# Flash-Memory.net
KiCad netlist of a schematic drawn in Altium Designer
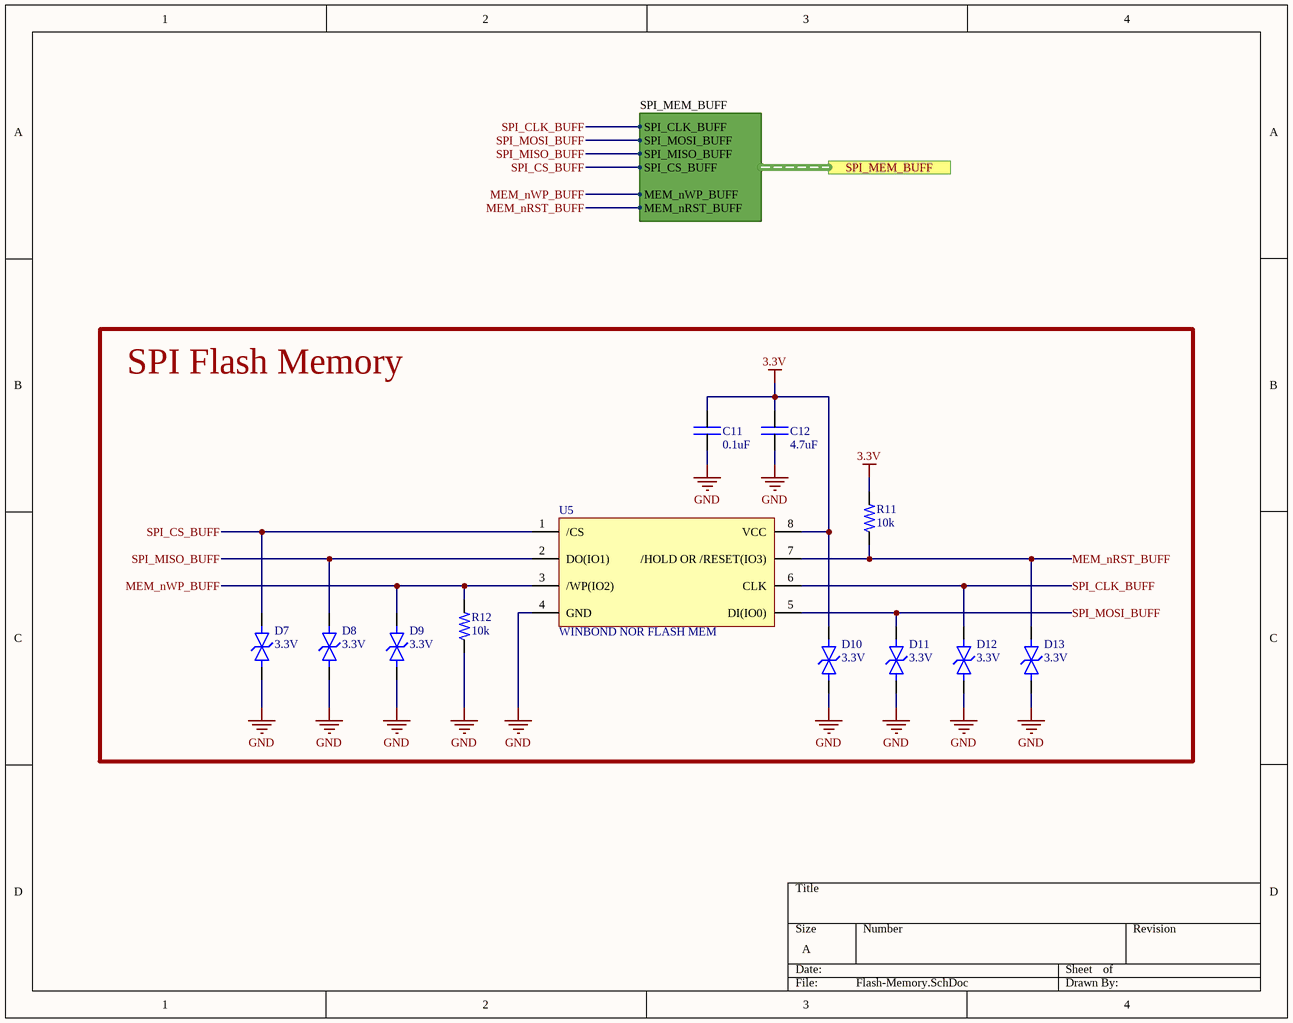
[diagram p0: Flash-Memory.SchDoc]

(export (version "E")
  (design (tool "Eeschema 10.0.6"))
  (components
    (comp (ref "C11")
      (value "0.1uF")
      (footprint "Christmas-2024_TSO-PCB:0402C")
      (description "Capacitor")
      (fields (field (name "MFR") "Samsung") (field (name "Comment") "CAP"))
      (libsource (lib "Christmas-2024_TSO-PCB") (part "CAP"))
    )
    (comp (ref "C12")
      (value "4.7uF")
      (footprint "Christmas-2024_TSO-PCB:0402C")
      (description "Capacitor")
      (fields (field (name "MFR") "Samsung") (field (name "Comment") "CAP"))
      (libsource (lib "Christmas-2024_TSO-PCB") (part "CAP"))
    )
    (comp (ref "D7")
      (value "DESD3V3E1BL-7B")
      (footprint "Christmas-2024_TSO-PCB:0402-TVS")
      (description "TVS DIODE 3.3VWM 7VC DFN1006-2")
      (fields (field (name "MFR") "Diodes Incorporated") (field (name "VRS") "3.3V"))
      (libsource (lib "Christmas-2024_TSO-PCB") (part "TVS Diode 3.3V Bi"))
    )
    (comp (ref "D8")
      (value "DESD3V3E1BL-7B")
      (footprint "Christmas-2024_TSO-PCB:0402-TVS")
      (description "TVS DIODE 3.3VWM 7VC DFN1006-2")
      (fields (field (name "MFR") "Diodes Incorporated") (field (name "VRS") "3.3V"))
      (libsource (lib "Christmas-2024_TSO-PCB") (part "TVS Diode 3.3V Bi"))
    )
    (comp (ref "D9")
      (value "DESD3V3E1BL-7B")
      (footprint "Christmas-2024_TSO-PCB:0402-TVS")
      (description "TVS DIODE 3.3VWM 7VC DFN1006-2")
      (fields (field (name "MFR") "Diodes Incorporated") (field (name "VRS") "3.3V"))
      (libsource (lib "Christmas-2024_TSO-PCB") (part "TVS Diode 3.3V Bi"))
    )
    (comp (ref "D10")
      (value "DESD3V3E1BL-7B")
      (footprint "Christmas-2024_TSO-PCB:0402-TVS")
      (description "TVS DIODE 3.3VWM 7VC DFN1006-2")
      (fields (field (name "MFR") "Diodes Incorporated") (field (name "VRS") "3.3V"))
      (libsource (lib "Christmas-2024_TSO-PCB") (part "TVS Diode 3.3V Bi"))
    )
    (comp (ref "D11")
      (value "DESD3V3E1BL-7B")
      (footprint "Christmas-2024_TSO-PCB:0402-TVS")
      (description "TVS DIODE 3.3VWM 7VC DFN1006-2")
      (fields (field (name "MFR") "Diodes Incorporated") (field (name "VRS") "3.3V"))
      (libsource (lib "Christmas-2024_TSO-PCB") (part "TVS Diode 3.3V Bi"))
    )
    (comp (ref "D12")
      (value "DESD3V3E1BL-7B")
      (footprint "Christmas-2024_TSO-PCB:0402-TVS")
      (description "TVS DIODE 3.3VWM 7VC DFN1006-2")
      (fields (field (name "MFR") "Diodes Incorporated") (field (name "VRS") "3.3V"))
      (libsource (lib "Christmas-2024_TSO-PCB") (part "TVS Diode 3.3V Bi"))
    )
    (comp (ref "D13")
      (value "DESD3V3E1BL-7B")
      (footprint "Christmas-2024_TSO-PCB:0402-TVS")
      (description "TVS DIODE 3.3VWM 7VC DFN1006-2")
      (fields (field (name "MFR") "Diodes Incorporated") (field (name "VRS") "3.3V"))
      (libsource (lib "Christmas-2024_TSO-PCB") (part "TVS Diode 3.3V Bi"))
    )
    (comp (ref "R11")
      (value "10k")
      (footprint "Christmas-2024_TSO-PCB:0402R")
      (description "Resistor")
      (fields (field (name "MFR") "YAGEO") (field (name "Comment") "RES"))
      (libsource (lib "Christmas-2024_TSO-PCB") (part "RES"))
    )
    (comp (ref "R12")
      (value "10k")
      (footprint "Christmas-2024_TSO-PCB:0402R")
      (description "Resistor")
      (fields (field (name "MFR") "YAGEO") (field (name "Comment") "RES"))
      (libsource (lib "Christmas-2024_TSO-PCB") (part "RES"))
    )
    (comp (ref "U5")
      (value "WINBOND NOR FLASH MEM")
      (footprint "Christmas-2024_TSO-PCB:8-SOIC")
      (description "FLASH - NOR Memory IC SPI, 128 Mbit")
      (fields (field (name "MFR") "Winbond"))
      (libsource (lib "Christmas-2024_TSO-PCB") (part "WINBOND NOR FLASH MEM"))
    )
  )
  (nets
    (net (code "2") (name "/MEM_nRST_BUFF") (class "Default")
      (node (ref "D13") (pin "1") (pinfunction "1_1") (pintype "passive"))
      (node (ref "R11") (pin "1") (pinfunction "1_1") (pintype "passive"))
      (node (ref "U5") (pin "7") (pinfunction "/HOLD_OR_/RESET(IO3)_7") (pintype "passive"))
    )
    (net (code "3") (name "/MEM_nWP_BUFF") (class "Default")
      (node (ref "D9") (pin "1") (pinfunction "1_1") (pintype "passive"))
      (node (ref "R12") (pin "2") (pinfunction "2_2") (pintype "passive"))
      (node (ref "U5") (pin "3") (pinfunction "/WP(IO2)_3") (pintype "passive"))
    )
    (net (code "4") (name "/SPI_CLK_BUFF") (class "Default")
      (node (ref "D12") (pin "1") (pinfunction "1_1") (pintype "passive"))
      (node (ref "U5") (pin "6") (pinfunction "CLK_6") (pintype "passive"))
    )
    (net (code "5") (name "/SPI_CS_BUFF") (class "Default")
      (node (ref "D7") (pin "1") (pinfunction "1_1") (pintype "passive"))
      (node (ref "U5") (pin "1") (pinfunction "/CS_1") (pintype "passive"))
    )
    (net (code "6") (name "/SPI_MISO_BUFF") (class "Default")
      (node (ref "D8") (pin "1") (pinfunction "1_1") (pintype "passive"))
      (node (ref "U5") (pin "2") (pinfunction "DO(IO1)_2") (pintype "passive"))
    )
    (net (code "7") (name "/SPI_MOSI_BUFF") (class "Default")
      (node (ref "D11") (pin "1") (pinfunction "1_1") (pintype "passive"))
      (node (ref "U5") (pin "5") (pinfunction "DI(IO0)_5") (pintype "passive"))
    )
    (net (code "9") (name "3.3V") (class "Default")
      (node (ref "C11") (pin "2") (pinfunction "2_2") (pintype "passive"))
      (node (ref "C12") (pin "2") (pinfunction "2_2") (pintype "passive"))
      (node (ref "D10") (pin "1") (pinfunction "1_1") (pintype "passive"))
      (node (ref "R11") (pin "2") (pinfunction "2_2") (pintype "passive"))
      (node (ref "U5") (pin "8") (pinfunction "VCC_8") (pintype "power_in"))
    )
    (net (code "10") (name "GND") (class "Default")
      (node (ref "C11") (pin "1") (pinfunction "1_1") (pintype "passive"))
      (node (ref "C12") (pin "1") (pinfunction "1_1") (pintype "passive"))
      (node (ref "D10") (pin "2") (pinfunction "2_2") (pintype "passive"))
      (node (ref "D11") (pin "2") (pinfunction "2_2") (pintype "passive"))
      (node (ref "D12") (pin "2") (pinfunction "2_2") (pintype "passive"))
      (node (ref "D13") (pin "2") (pinfunction "2_2") (pintype "passive"))
      (node (ref "D7") (pin "2") (pinfunction "2_2") (pintype "passive"))
      (node (ref "D8") (pin "2") (pinfunction "2_2") (pintype "passive"))
      (node (ref "D9") (pin "2") (pinfunction "2_2") (pintype "passive"))
      (node (ref "R12") (pin "1") (pinfunction "1_1") (pintype "passive"))
      (node (ref "U5") (pin "4") (pinfunction "GND_4") (pintype "power_in"))
    )
  )
)
